# Robotics_Ring_Light.net
KiCad netlist of a schematic drawn in EAGLE
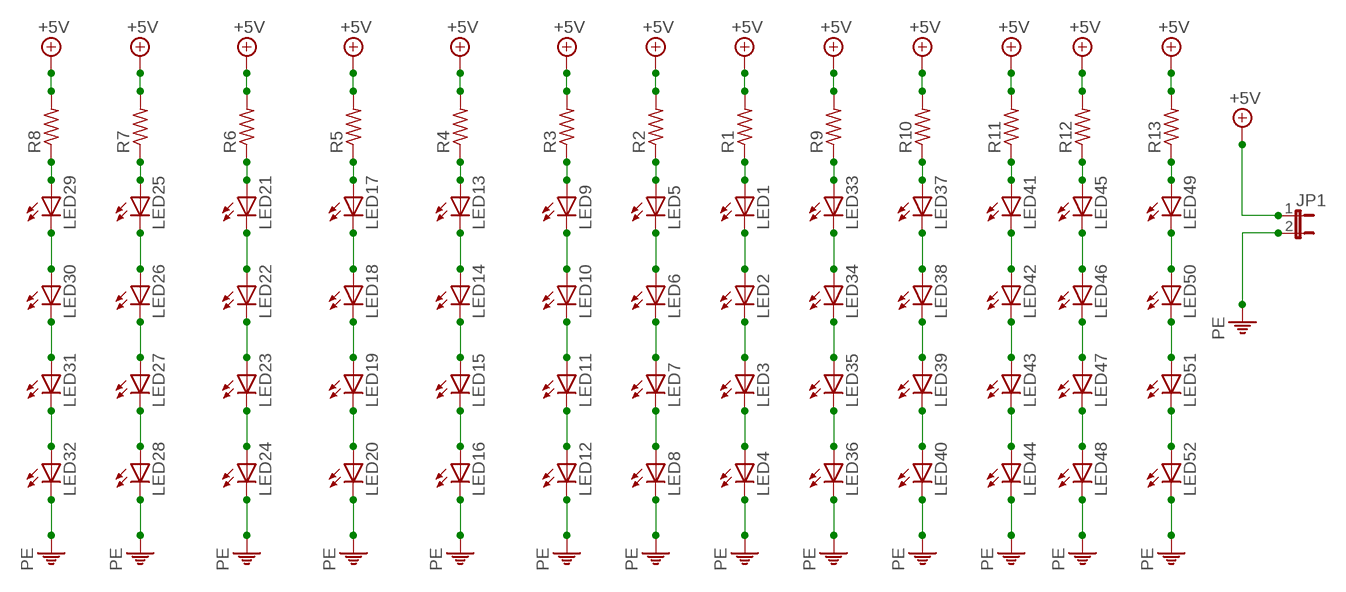
[diagram p0: schematic, sheet 1]

(export (version "E")
  (design (tool "Eeschema 10.0.6"))
  (components
    (comp (ref "JP1")
      (value "JP1E")
      (footprint "eagle-import:JP1")
      (libsource (lib "eagle-import") (part "JP1E"))
    )
    (comp (ref "LED1")
      (value "LED5MM")
      (footprint "eagle-import:LED5MM")
      (libsource (lib "eagle-import") (part "LED5MM"))
    )
    (comp (ref "LED2")
      (value "LED5MM")
      (footprint "eagle-import:LED5MM")
      (libsource (lib "eagle-import") (part "LED5MM"))
    )
    (comp (ref "LED3")
      (value "LED5MM")
      (footprint "eagle-import:LED5MM")
      (libsource (lib "eagle-import") (part "LED5MM"))
    )
    (comp (ref "LED4")
      (value "LED5MM")
      (footprint "eagle-import:LED5MM")
      (libsource (lib "eagle-import") (part "LED5MM"))
    )
    (comp (ref "LED5")
      (value "LED5MM")
      (footprint "eagle-import:LED5MM")
      (libsource (lib "eagle-import") (part "LED5MM"))
    )
    (comp (ref "LED6")
      (value "LED5MM")
      (footprint "eagle-import:LED5MM")
      (libsource (lib "eagle-import") (part "LED5MM"))
    )
    (comp (ref "LED7")
      (value "LED5MM")
      (footprint "eagle-import:LED5MM")
      (libsource (lib "eagle-import") (part "LED5MM"))
    )
    (comp (ref "LED8")
      (value "LED5MM")
      (footprint "eagle-import:LED5MM")
      (libsource (lib "eagle-import") (part "LED5MM"))
    )
    (comp (ref "LED9")
      (value "LED5MM")
      (footprint "eagle-import:LED5MM")
      (libsource (lib "eagle-import") (part "LED5MM"))
    )
    (comp (ref "LED10")
      (value "LED5MM")
      (footprint "eagle-import:LED5MM")
      (libsource (lib "eagle-import") (part "LED5MM"))
    )
    (comp (ref "LED11")
      (value "LED5MM")
      (footprint "eagle-import:LED5MM")
      (libsource (lib "eagle-import") (part "LED5MM"))
    )
    (comp (ref "LED12")
      (value "LED5MM")
      (footprint "eagle-import:LED5MM")
      (libsource (lib "eagle-import") (part "LED5MM"))
    )
    (comp (ref "LED13")
      (value "LED5MM")
      (footprint "eagle-import:LED5MM")
      (libsource (lib "eagle-import") (part "LED5MM"))
    )
    (comp (ref "LED14")
      (value "LED5MM")
      (footprint "eagle-import:LED5MM")
      (libsource (lib "eagle-import") (part "LED5MM"))
    )
    (comp (ref "LED15")
      (value "LED5MM")
      (footprint "eagle-import:LED5MM")
      (libsource (lib "eagle-import") (part "LED5MM"))
    )
    (comp (ref "LED16")
      (value "LED5MM")
      (footprint "eagle-import:LED5MM")
      (libsource (lib "eagle-import") (part "LED5MM"))
    )
    (comp (ref "LED17")
      (value "LED5MM")
      (footprint "eagle-import:LED5MM")
      (libsource (lib "eagle-import") (part "LED5MM"))
    )
    (comp (ref "LED18")
      (value "LED5MM")
      (footprint "eagle-import:LED5MM")
      (libsource (lib "eagle-import") (part "LED5MM"))
    )
    (comp (ref "LED19")
      (value "LED5MM")
      (footprint "eagle-import:LED5MM")
      (libsource (lib "eagle-import") (part "LED5MM"))
    )
    (comp (ref "LED20")
      (value "LED5MM")
      (footprint "eagle-import:LED5MM")
      (libsource (lib "eagle-import") (part "LED5MM"))
    )
    (comp (ref "LED21")
      (value "LED5MM")
      (footprint "eagle-import:LED5MM")
      (libsource (lib "eagle-import") (part "LED5MM"))
    )
    (comp (ref "LED22")
      (value "LED5MM")
      (footprint "eagle-import:LED5MM")
      (libsource (lib "eagle-import") (part "LED5MM"))
    )
    (comp (ref "LED23")
      (value "LED5MM")
      (footprint "eagle-import:LED5MM")
      (libsource (lib "eagle-import") (part "LED5MM"))
    )
    (comp (ref "LED24")
      (value "LED5MM")
      (footprint "eagle-import:LED5MM")
      (libsource (lib "eagle-import") (part "LED5MM"))
    )
    (comp (ref "LED25")
      (value "LED5MM")
      (footprint "eagle-import:LED5MM")
      (libsource (lib "eagle-import") (part "LED5MM"))
    )
    (comp (ref "LED26")
      (value "LED5MM")
      (footprint "eagle-import:LED5MM")
      (libsource (lib "eagle-import") (part "LED5MM"))
    )
    (comp (ref "LED27")
      (value "LED5MM")
      (footprint "eagle-import:LED5MM")
      (libsource (lib "eagle-import") (part "LED5MM"))
    )
    (comp (ref "LED28")
      (value "LED5MM")
      (footprint "eagle-import:LED5MM")
      (libsource (lib "eagle-import") (part "LED5MM"))
    )
    (comp (ref "LED29")
      (value "LED5MM")
      (footprint "eagle-import:LED5MM")
      (libsource (lib "eagle-import") (part "LED5MM"))
    )
    (comp (ref "LED30")
      (value "LED5MM")
      (footprint "eagle-import:LED5MM")
      (libsource (lib "eagle-import") (part "LED5MM"))
    )
    (comp (ref "LED31")
      (value "LED5MM")
      (footprint "eagle-import:LED5MM")
      (libsource (lib "eagle-import") (part "LED5MM"))
    )
    (comp (ref "LED32")
      (value "LED5MM")
      (footprint "eagle-import:LED5MM")
      (libsource (lib "eagle-import") (part "LED5MM"))
    )
    (comp (ref "LED33")
      (value "LED5MM")
      (footprint "eagle-import:LED5MM")
      (libsource (lib "eagle-import") (part "LED5MM"))
    )
    (comp (ref "LED34")
      (value "LED5MM")
      (footprint "eagle-import:LED5MM")
      (libsource (lib "eagle-import") (part "LED5MM"))
    )
    (comp (ref "LED35")
      (value "LED5MM")
      (footprint "eagle-import:LED5MM")
      (libsource (lib "eagle-import") (part "LED5MM"))
    )
    (comp (ref "LED36")
      (value "LED5MM")
      (footprint "eagle-import:LED5MM")
      (libsource (lib "eagle-import") (part "LED5MM"))
    )
    (comp (ref "LED37")
      (value "LED5MM")
      (footprint "eagle-import:LED5MM")
      (libsource (lib "eagle-import") (part "LED5MM"))
    )
    (comp (ref "LED38")
      (value "LED5MM")
      (footprint "eagle-import:LED5MM")
      (libsource (lib "eagle-import") (part "LED5MM"))
    )
    (comp (ref "LED39")
      (value "LED5MM")
      (footprint "eagle-import:LED5MM")
      (libsource (lib "eagle-import") (part "LED5MM"))
    )
    (comp (ref "LED40")
      (value "LED5MM")
      (footprint "eagle-import:LED5MM")
      (libsource (lib "eagle-import") (part "LED5MM"))
    )
    (comp (ref "LED41")
      (value "LED5MM")
      (footprint "eagle-import:LED5MM")
      (libsource (lib "eagle-import") (part "LED5MM"))
    )
    (comp (ref "LED42")
      (value "LED5MM")
      (footprint "eagle-import:LED5MM")
      (libsource (lib "eagle-import") (part "LED5MM"))
    )
    (comp (ref "LED43")
      (value "LED5MM")
      (footprint "eagle-import:LED5MM")
      (libsource (lib "eagle-import") (part "LED5MM"))
    )
    (comp (ref "LED44")
      (value "LED5MM")
      (footprint "eagle-import:LED5MM")
      (libsource (lib "eagle-import") (part "LED5MM"))
    )
    (comp (ref "LED45")
      (value "LED5MM")
      (footprint "eagle-import:LED5MM")
      (libsource (lib "eagle-import") (part "LED5MM"))
    )
    (comp (ref "LED46")
      (value "LED5MM")
      (footprint "eagle-import:LED5MM")
      (libsource (lib "eagle-import") (part "LED5MM"))
    )
    (comp (ref "LED47")
      (value "LED5MM")
      (footprint "eagle-import:LED5MM")
      (libsource (lib "eagle-import") (part "LED5MM"))
    )
    (comp (ref "LED48")
      (value "LED5MM")
      (footprint "eagle-import:LED5MM")
      (libsource (lib "eagle-import") (part "LED5MM"))
    )
    (comp (ref "LED49")
      (value "LED5MM")
      (footprint "eagle-import:LED5MM")
      (libsource (lib "eagle-import") (part "LED5MM"))
    )
    (comp (ref "LED50")
      (value "LED5MM")
      (footprint "eagle-import:LED5MM")
      (libsource (lib "eagle-import") (part "LED5MM"))
    )
    (comp (ref "LED51")
      (value "LED5MM")
      (footprint "eagle-import:LED5MM")
      (libsource (lib "eagle-import") (part "LED5MM"))
    )
    (comp (ref "LED52")
      (value "LED5MM")
      (footprint "eagle-import:LED5MM")
      (libsource (lib "eagle-import") (part "LED5MM"))
    )
    (comp (ref "R1")
      (value "R-US_0207/10")
      (footprint "eagle-import:0207_10")
      (libsource (lib "eagle-import") (part "R-US_0207/10"))
    )
    (comp (ref "R2")
      (value "R-US_0207/10")
      (footprint "eagle-import:0207_10")
      (libsource (lib "eagle-import") (part "R-US_0207/10"))
    )
    (comp (ref "R3")
      (value "R-US_0207/10")
      (footprint "eagle-import:0207_10")
      (libsource (lib "eagle-import") (part "R-US_0207/10"))
    )
    (comp (ref "R4")
      (value "R-US_0207/10")
      (footprint "eagle-import:0207_10")
      (libsource (lib "eagle-import") (part "R-US_0207/10"))
    )
    (comp (ref "R5")
      (value "R-US_0207/10")
      (footprint "eagle-import:0207_10")
      (libsource (lib "eagle-import") (part "R-US_0207/10"))
    )
    (comp (ref "R6")
      (value "R-US_0207/10")
      (footprint "eagle-import:0207_10")
      (libsource (lib "eagle-import") (part "R-US_0207/10"))
    )
    (comp (ref "R7")
      (value "R-US_0207/10")
      (footprint "eagle-import:0207_10")
      (libsource (lib "eagle-import") (part "R-US_0207/10"))
    )
    (comp (ref "R8")
      (value "R-US_0207/10")
      (footprint "eagle-import:0207_10")
      (libsource (lib "eagle-import") (part "R-US_0207/10"))
    )
    (comp (ref "R9")
      (value "R-US_0207/10")
      (footprint "eagle-import:0207_10")
      (libsource (lib "eagle-import") (part "R-US_0207/10"))
    )
    (comp (ref "R10")
      (value "R-US_0207/10")
      (footprint "eagle-import:0207_10")
      (libsource (lib "eagle-import") (part "R-US_0207/10"))
    )
    (comp (ref "R11")
      (value "R-US_0207/10")
      (footprint "eagle-import:0207_10")
      (libsource (lib "eagle-import") (part "R-US_0207/10"))
    )
    (comp (ref "R12")
      (value "R-US_0207/10")
      (footprint "eagle-import:0207_10")
      (libsource (lib "eagle-import") (part "R-US_0207/10"))
    )
    (comp (ref "R13")
      (value "R-US_0207/10")
      (footprint "eagle-import:0207_10")
      (libsource (lib "eagle-import") (part "R-US_0207/10"))
    )
  )
  (nets
    (net (code "1") (name "+5V") (class "Default")
      (node (ref "JP1") (pin "1") (pinfunction "1_1") (pintype "passive"))
      (node (ref "R1") (pin "2") (pinfunction "2_2") (pintype "passive"))
      (node (ref "R10") (pin "2") (pinfunction "2_2") (pintype "passive"))
      (node (ref "R11") (pin "2") (pinfunction "2_2") (pintype "passive"))
      (node (ref "R12") (pin "2") (pinfunction "2_2") (pintype "passive"))
      (node (ref "R13") (pin "2") (pinfunction "2_2") (pintype "passive"))
      (node (ref "R2") (pin "2") (pinfunction "2_2") (pintype "passive"))
      (node (ref "R3") (pin "2") (pinfunction "2_2") (pintype "passive"))
      (node (ref "R4") (pin "2") (pinfunction "2_2") (pintype "passive"))
      (node (ref "R5") (pin "2") (pinfunction "2_2") (pintype "passive"))
      (node (ref "R6") (pin "2") (pinfunction "2_2") (pintype "passive"))
      (node (ref "R7") (pin "2") (pinfunction "2_2") (pintype "passive"))
      (node (ref "R8") (pin "2") (pinfunction "2_2") (pintype "passive"))
      (node (ref "R9") (pin "2") (pinfunction "2_2") (pintype "passive"))
    )
    (net (code "2") (name "Net-(LED1-C)") (class "Default")
      (node (ref "LED1") (pin "K") (pinfunction "C_K") (pintype "passive"))
      (node (ref "LED2") (pin "A") (pinfunction "A_A") (pintype "passive"))
    )
    (net (code "3") (name "Net-(LED1-PadA)") (class "Default")
      (node (ref "LED1") (pin "A") (pinfunction "A_A") (pintype "passive"))
      (node (ref "R1") (pin "1") (pinfunction "1_1") (pintype "passive"))
    )
    (net (code "4") (name "Net-(LED2-C)") (class "Default")
      (node (ref "LED2") (pin "K") (pinfunction "C_K") (pintype "passive"))
      (node (ref "LED3") (pin "A") (pinfunction "A_A") (pintype "passive"))
    )
    (net (code "5") (name "Net-(LED3-C)") (class "Default")
      (node (ref "LED3") (pin "K") (pinfunction "C_K") (pintype "passive"))
      (node (ref "LED4") (pin "A") (pinfunction "A_A") (pintype "passive"))
    )
    (net (code "6") (name "Net-(LED5-C)") (class "Default")
      (node (ref "LED5") (pin "K") (pinfunction "C_K") (pintype "passive"))
      (node (ref "LED6") (pin "A") (pinfunction "A_A") (pintype "passive"))
    )
    (net (code "7") (name "Net-(LED5-PadA)") (class "Default")
      (node (ref "LED5") (pin "A") (pinfunction "A_A") (pintype "passive"))
      (node (ref "R2") (pin "1") (pinfunction "1_1") (pintype "passive"))
    )
    (net (code "8") (name "Net-(LED6-C)") (class "Default")
      (node (ref "LED6") (pin "K") (pinfunction "C_K") (pintype "passive"))
      (node (ref "LED7") (pin "A") (pinfunction "A_A") (pintype "passive"))
    )
    (net (code "9") (name "Net-(LED7-C)") (class "Default")
      (node (ref "LED7") (pin "K") (pinfunction "C_K") (pintype "passive"))
      (node (ref "LED8") (pin "A") (pinfunction "A_A") (pintype "passive"))
    )
    (net (code "10") (name "Net-(LED9-C)") (class "Default")
      (node (ref "LED10") (pin "A") (pinfunction "A_A") (pintype "passive"))
      (node (ref "LED9") (pin "K") (pinfunction "C_K") (pintype "passive"))
    )
    (net (code "11") (name "Net-(LED9-PadA)") (class "Default")
      (node (ref "LED9") (pin "A") (pinfunction "A_A") (pintype "passive"))
      (node (ref "R3") (pin "1") (pinfunction "1_1") (pintype "passive"))
    )
    (net (code "12") (name "Net-(LED10-C)") (class "Default")
      (node (ref "LED10") (pin "K") (pinfunction "C_K") (pintype "passive"))
      (node (ref "LED11") (pin "A") (pinfunction "A_A") (pintype "passive"))
    )
    (net (code "13") (name "Net-(LED11-C)") (class "Default")
      (node (ref "LED11") (pin "K") (pinfunction "C_K") (pintype "passive"))
      (node (ref "LED12") (pin "A") (pinfunction "A_A") (pintype "passive"))
    )
    (net (code "14") (name "Net-(LED13-C)") (class "Default")
      (node (ref "LED13") (pin "K") (pinfunction "C_K") (pintype "passive"))
      (node (ref "LED14") (pin "A") (pinfunction "A_A") (pintype "passive"))
    )
    (net (code "15") (name "Net-(LED13-PadA)") (class "Default")
      (node (ref "LED13") (pin "A") (pinfunction "A_A") (pintype "passive"))
      (node (ref "R4") (pin "1") (pinfunction "1_1") (pintype "passive"))
    )
    (net (code "16") (name "Net-(LED14-C)") (class "Default")
      (node (ref "LED14") (pin "K") (pinfunction "C_K") (pintype "passive"))
      (node (ref "LED15") (pin "A") (pinfunction "A_A") (pintype "passive"))
    )
    (net (code "17") (name "Net-(LED15-C)") (class "Default")
      (node (ref "LED15") (pin "K") (pinfunction "C_K") (pintype "passive"))
      (node (ref "LED16") (pin "A") (pinfunction "A_A") (pintype "passive"))
    )
    (net (code "18") (name "Net-(LED17-C)") (class "Default")
      (node (ref "LED17") (pin "K") (pinfunction "C_K") (pintype "passive"))
      (node (ref "LED18") (pin "A") (pinfunction "A_A") (pintype "passive"))
    )
    (net (code "19") (name "Net-(LED17-PadA)") (class "Default")
      (node (ref "LED17") (pin "A") (pinfunction "A_A") (pintype "passive"))
      (node (ref "R5") (pin "1") (pinfunction "1_1") (pintype "passive"))
    )
    (net (code "20") (name "Net-(LED18-C)") (class "Default")
      (node (ref "LED18") (pin "K") (pinfunction "C_K") (pintype "passive"))
      (node (ref "LED19") (pin "A") (pinfunction "A_A") (pintype "passive"))
    )
    (net (code "21") (name "Net-(LED19-C)") (class "Default")
      (node (ref "LED19") (pin "K") (pinfunction "C_K") (pintype "passive"))
      (node (ref "LED20") (pin "A") (pinfunction "A_A") (pintype "passive"))
    )
    (net (code "22") (name "Net-(LED21-C)") (class "Default")
      (node (ref "LED21") (pin "K") (pinfunction "C_K") (pintype "passive"))
      (node (ref "LED22") (pin "A") (pinfunction "A_A") (pintype "passive"))
    )
    (net (code "23") (name "Net-(LED21-PadA)") (class "Default")
      (node (ref "LED21") (pin "A") (pinfunction "A_A") (pintype "passive"))
      (node (ref "R6") (pin "1") (pinfunction "1_1") (pintype "passive"))
    )
    (net (code "24") (name "Net-(LED22-C)") (class "Default")
      (node (ref "LED22") (pin "K") (pinfunction "C_K") (pintype "passive"))
      (node (ref "LED23") (pin "A") (pinfunction "A_A") (pintype "passive"))
    )
    (net (code "25") (name "Net-(LED23-C)") (class "Default")
      (node (ref "LED23") (pin "K") (pinfunction "C_K") (pintype "passive"))
      (node (ref "LED24") (pin "A") (pinfunction "A_A") (pintype "passive"))
    )
    (net (code "26") (name "Net-(LED25-C)") (class "Default")
      (node (ref "LED25") (pin "K") (pinfunction "C_K") (pintype "passive"))
      (node (ref "LED26") (pin "A") (pinfunction "A_A") (pintype "passive"))
    )
    (net (code "27") (name "Net-(LED25-PadA)") (class "Default")
      (node (ref "LED25") (pin "A") (pinfunction "A_A") (pintype "passive"))
      (node (ref "R7") (pin "1") (pinfunction "1_1") (pintype "passive"))
    )
    (net (code "28") (name "Net-(LED26-C)") (class "Default")
      (node (ref "LED26") (pin "K") (pinfunction "C_K") (pintype "passive"))
      (node (ref "LED27") (pin "A") (pinfunction "A_A") (pintype "passive"))
    )
    (net (code "29") (name "Net-(LED27-C)") (class "Default")
      (node (ref "LED27") (pin "K") (pinfunction "C_K") (pintype "passive"))
      (node (ref "LED28") (pin "A") (pinfunction "A_A") (pintype "passive"))
    )
    (net (code "30") (name "Net-(LED29-C)") (class "Default")
      (node (ref "LED29") (pin "K") (pinfunction "C_K") (pintype "passive"))
      (node (ref "LED30") (pin "A") (pinfunction "A_A") (pintype "passive"))
    )
    (net (code "31") (name "Net-(LED29-PadA)") (class "Default")
      (node (ref "LED29") (pin "A") (pinfunction "A_A") (pintype "passive"))
      (node (ref "R8") (pin "1") (pinfunction "1_1") (pintype "passive"))
    )
    (net (code "32") (name "Net-(LED30-C)") (class "Default")
      (node (ref "LED30") (pin "K") (pinfunction "C_K") (pintype "passive"))
      (node (ref "LED31") (pin "A") (pinfunction "A_A") (pintype "passive"))
    )
    (net (code "33") (name "Net-(LED31-C)") (class "Default")
      (node (ref "LED31") (pin "K") (pinfunction "C_K") (pintype "passive"))
      (node (ref "LED32") (pin "A") (pinfunction "A_A") (pintype "passive"))
    )
    (net (code "34") (name "Net-(LED33-C)") (class "Default")
      (node (ref "LED33") (pin "K") (pinfunction "C_K") (pintype "passive"))
      (node (ref "LED34") (pin "A") (pinfunction "A_A") (pintype "passive"))
    )
    (net (code "35") (name "Net-(LED33-PadA)") (class "Default")
      (node (ref "LED33") (pin "A") (pinfunction "A_A") (pintype "passive"))
      (node (ref "R9") (pin "1") (pinfunction "1_1") (pintype "passive"))
    )
    (net (code "36") (name "Net-(LED34-C)") (class "Default")
      (node (ref "LED34") (pin "K") (pinfunction "C_K") (pintype "passive"))
      (node (ref "LED35") (pin "A") (pinfunction "A_A") (pintype "passive"))
    )
    (net (code "37") (name "Net-(LED35-C)") (class "Default")
      (node (ref "LED35") (pin "K") (pinfunction "C_K") (pintype "passive"))
      (node (ref "LED36") (pin "A") (pinfunction "A_A") (pintype "passive"))
    )
    (net (code "38") (name "Net-(LED37-C)") (class "Default")
      (node (ref "LED37") (pin "K") (pinfunction "C_K") (pintype "passive"))
      (node (ref "LED38") (pin "A") (pinfunction "A_A") (pintype "passive"))
    )
    (net (code "39") (name "Net-(LED37-PadA)") (class "Default")
      (node (ref "LED37") (pin "A") (pinfunction "A_A") (pintype "passive"))
      (node (ref "R10") (pin "1") (pinfunction "1_1") (pintype "passive"))
    )
    (net (code "40") (name "Net-(LED38-C)") (class "Default")
      (node (ref "LED38") (pin "K") (pinfunction "C_K") (pintype "passive"))
      (node (ref "LED39") (pin "A") (pinfunction "A_A") (pintype "passive"))
    )
    (net (code "41") (name "Net-(LED39-C)") (class "Default")
      (node (ref "LED39") (pin "K") (pinfunction "C_K") (pintype "passive"))
      (node (ref "LED40") (pin "A") (pinfunction "A_A") (pintype "passive"))
    )
    (net (code "42") (name "Net-(LED41-C)") (class "Default")
      (node (ref "LED41") (pin "K") (pinfunction "C_K") (pintype "passive"))
      (node (ref "LED42") (pin "A") (pinfunction "A_A") (pintype "passive"))
    )
    (net (code "43") (name "Net-(LED41-PadA)") (class "Default")
      (node (ref "LED41") (pin "A") (pinfunction "A_A") (pintype "passive"))
      (node (ref "R11") (pin "1") (pinfunction "1_1") (pintype "passive"))
    )
    (net (code "44") (name "Net-(LED42-C)") (class "Default")
      (node (ref "LED42") (pin "K") (pinfunction "C_K") (pintype "passive"))
      (node (ref "LED43") (pin "A") (pinfunction "A_A") (pintype "passive"))
    )
    (net (code "45") (name "Net-(LED43-C)") (class "Default")
      (node (ref "LED43") (pin "K") (pinfunction "C_K") (pintype "passive"))
      (node (ref "LED44") (pin "A") (pinfunction "A_A") (pintype "passive"))
    )
    (net (code "46") (name "Net-(LED45-C)") (class "Default")
      (node (ref "LED45") (pin "K") (pinfunction "C_K") (pintype "passive"))
      (node (ref "LED46") (pin "A") (pinfunction "A_A") (pintype "passive"))
    )
    (net (code "47") (name "Net-(LED45-PadA)") (class "Default")
      (node (ref "LED45") (pin "A") (pinfunction "A_A") (pintype "passive"))
      (node (ref "R12") (pin "1") (pinfunction "1_1") (pintype "passive"))
    )
    (net (code "48") (name "Net-(LED46-C)") (class "Default")
      (node (ref "LED46") (pin "K") (pinfunction "C_K") (pintype "passive"))
      (node (ref "LED47") (pin "A") (pinfunction "A_A") (pintype "passive"))
    )
    (net (code "49") (name "Net-(LED47-C)") (class "Default")
      (node (ref "LED47") (pin "K") (pinfunction "C_K") (pintype "passive"))
      (node (ref "LED48") (pin "A") (pinfunction "A_A") (pintype "passive"))
    )
    (net (code "50") (name "Net-(LED49-C)") (class "Default")
      (node (ref "LED49") (pin "K") (pinfunction "C_K") (pintype "passive"))
      (node (ref "LED50") (pin "A") (pinfunction "A_A") (pintype "passive"))
    )
    (net (code "51") (name "Net-(LED49-PadA)") (class "Default")
      (node (ref "LED49") (pin "A") (pinfunction "A_A") (pintype "passive"))
      (node (ref "R13") (pin "1") (pinfunction "1_1") (pintype "passive"))
    )
    (net (code "52") (name "Net-(LED50-C)") (class "Default")
      (node (ref "LED50") (pin "K") (pinfunction "C_K") (pintype "passive"))
      (node (ref "LED51") (pin "A") (pinfunction "A_A") (pintype "passive"))
    )
    (net (code "53") (name "Net-(LED51-C)") (class "Default")
      (node (ref "LED51") (pin "K") (pinfunction "C_K") (pintype "passive"))
      (node (ref "LED52") (pin "A") (pinfunction "A_A") (pintype "passive"))
    )
    (net (code "54") (name "PE") (class "Default")
      (node (ref "JP1") (pin "2") (pinfunction "2_2") (pintype "passive"))
      (node (ref "LED12") (pin "K") (pinfunction "C_K") (pintype "passive"))
      (node (ref "LED16") (pin "K") (pinfunction "C_K") (pintype "passive"))
      (node (ref "LED20") (pin "K") (pinfunction "C_K") (pintype "passive"))
      (node (ref "LED24") (pin "K") (pinfunction "C_K") (pintype "passive"))
      (node (ref "LED28") (pin "K") (pinfunction "C_K") (pintype "passive"))
      (node (ref "LED32") (pin "K") (pinfunction "C_K") (pintype "passive"))
      (node (ref "LED36") (pin "K") (pinfunction "C_K") (pintype "passive"))
      (node (ref "LED4") (pin "K") (pinfunction "C_K") (pintype "passive"))
      (node (ref "LED40") (pin "K") (pinfunction "C_K") (pintype "passive"))
      (node (ref "LED44") (pin "K") (pinfunction "C_K") (pintype "passive"))
      (node (ref "LED48") (pin "K") (pinfunction "C_K") (pintype "passive"))
      (node (ref "LED52") (pin "K") (pinfunction "C_K") (pintype "passive"))
      (node (ref "LED8") (pin "K") (pinfunction "C_K") (pintype "passive"))
    )
  )
)
